# tb_projekt_rf433_shield_mini_revA.net
KiCad netlist of a schematic drawn in EAGLE
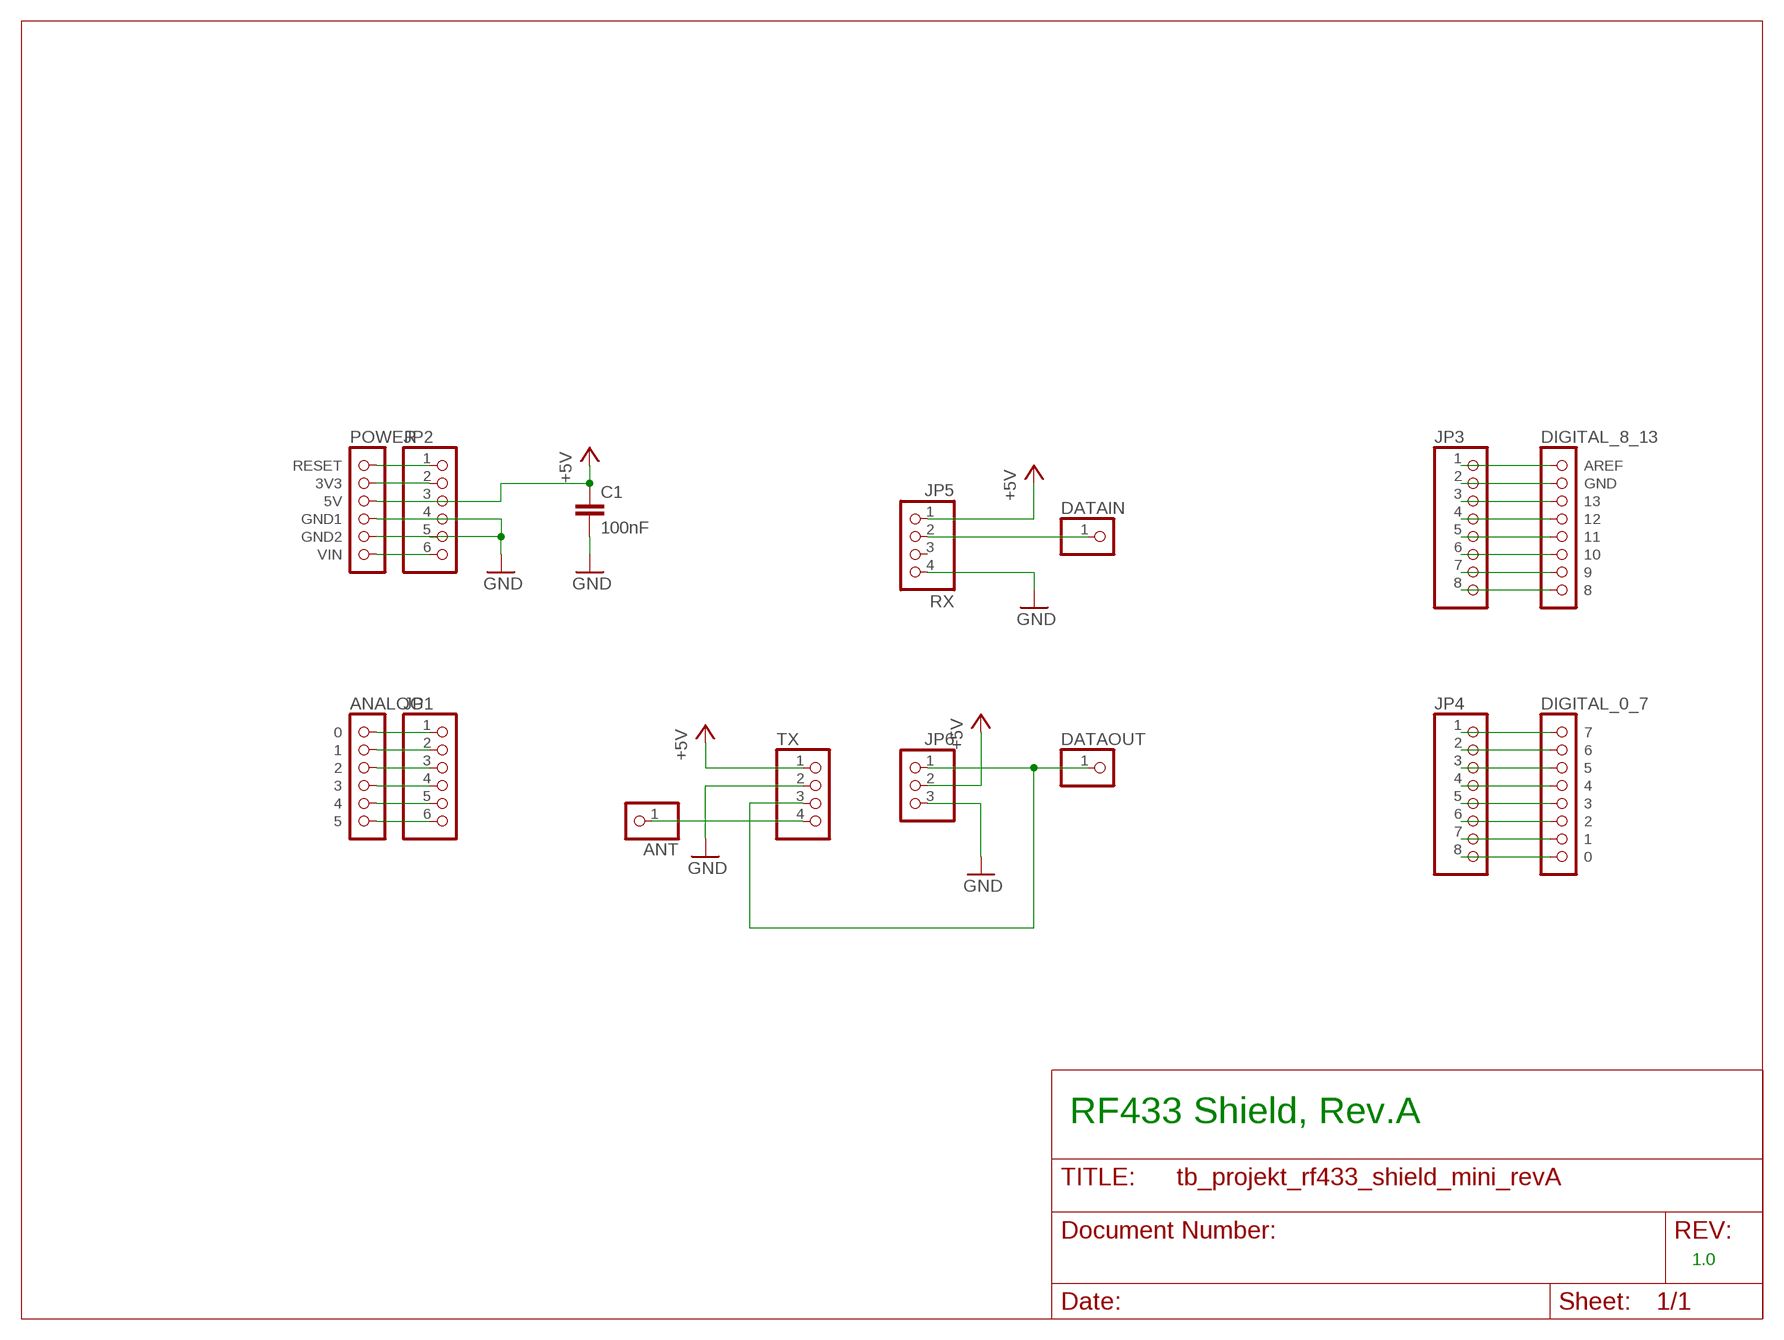
[diagram p0: schematic, sheet 1]

(export (version "E")
  (design (tool "Eeschema 10.0.6"))
  (components
    (comp (ref "ANT")
      (value "PINHD-1X1")
      (footprint "eagle-import:1X01")
      (libsource (lib "eagle-import") (part "PINHD-1X1"))
    )
    (comp (ref "C1")
      (value "100nF")
      (footprint "eagle-import:C025-024X044")
      (libsource (lib "eagle-import") (part "C-EU025-024X044"))
    )
    (comp (ref "DATAIN")
      (value "PINHD-1X1")
      (footprint "eagle-import:1X01")
      (libsource (lib "eagle-import") (part "PINHD-1X1"))
    )
    (comp (ref "DATAOUT")
      (value "PINHD-1X1")
      (footprint "eagle-import:1X01")
      (libsource (lib "eagle-import") (part "PINHD-1X1"))
    )
    (comp (ref "JP1")
      (value "PINHD-1X6")
      (footprint "eagle-import:1X06")
      (libsource (lib "eagle-import") (part "PINHD-1X6"))
    )
    (comp (ref "JP2")
      (value "PINHD-1X6")
      (footprint "eagle-import:1X06")
      (libsource (lib "eagle-import") (part "PINHD-1X6"))
    )
    (comp (ref "JP3")
      (value "PINHD-1X8")
      (footprint "eagle-import:1X08")
      (libsource (lib "eagle-import") (part "PINHD-1X8"))
    )
    (comp (ref "JP4")
      (value "PINHD-1X8")
      (footprint "eagle-import:1X08")
      (libsource (lib "eagle-import") (part "PINHD-1X8"))
    )
    (comp (ref "JP5")
      (value "RX")
      (footprint "eagle-import:1X04")
      (libsource (lib "eagle-import") (part "PINHD-1X4"))
    )
    (comp (ref "JP6")
      (value "PINHD-1X3")
      (footprint "eagle-import:1X03")
      (libsource (lib "eagle-import") (part "PINHD-1X3"))
    )
    (comp (ref "TX")
      (value "PINHD-1X4")
      (footprint "eagle-import:1X04")
      (libsource (lib "eagle-import") (part "PINHD-1X4"))
    )
    (comp (ref "U$1")
      (value "POWER")
      (footprint "eagle-import:1X06")
      (libsource (lib "eagle-import") (part "POWER"))
    )
    (comp (ref "U$2")
      (value "ANALOG")
      (footprint "eagle-import:1X06")
      (libsource (lib "eagle-import") (part "ANALOG"))
    )
    (comp (ref "U$3")
      (value "DIGITAL_0_7")
      (footprint "eagle-import:1X08")
      (libsource (lib "eagle-import") (part "DIGITAL_0_7"))
    )
    (comp (ref "U$4")
      (value "DIGITAL_8_13")
      (footprint "eagle-import:1X08")
      (libsource (lib "eagle-import") (part "DIGITAL_8_13"))
    )
  )
  (nets
    (net (code "1") (name "+5V") (class "Default")
      (node (ref "C1") (pin "1") (pinfunction "1_1") (pintype "passive"))
      (node (ref "JP2") (pin "3") (pinfunction "3_3") (pintype "passive"))
      (node (ref "JP5") (pin "1") (pinfunction "1_1") (pintype "passive"))
      (node (ref "JP6") (pin "2") (pinfunction "2_2") (pintype "passive"))
      (node (ref "TX") (pin "1") (pinfunction "1_1") (pintype "passive"))
      (node (ref "U$1") (pin "3") (pinfunction "5V_3") (pintype "passive"))
    )
    (net (code "2") (name "GND") (class "Default")
      (node (ref "C1") (pin "2") (pinfunction "2_2") (pintype "passive"))
      (node (ref "JP2") (pin "4") (pinfunction "4_4") (pintype "passive"))
      (node (ref "JP2") (pin "5") (pinfunction "5_5") (pintype "passive"))
      (node (ref "JP5") (pin "4") (pinfunction "4_4") (pintype "passive"))
      (node (ref "JP6") (pin "3") (pinfunction "3_3") (pintype "passive"))
      (node (ref "TX") (pin "2") (pinfunction "2_2") (pintype "passive"))
      (node (ref "U$1") (pin "4") (pinfunction "GND1_4") (pintype "passive"))
      (node (ref "U$1") (pin "5") (pinfunction "GND2_5") (pintype "passive"))
    )
    (net (code "3") (name "Net-(ANT-Pad1)") (class "Default")
      (node (ref "ANT") (pin "1") (pinfunction "1_1") (pintype "passive"))
      (node (ref "TX") (pin "4") (pinfunction "4_4") (pintype "passive"))
    )
    (net (code "4") (name "Net-(DATAIN-Pad1)") (class "Default")
      (node (ref "DATAIN") (pin "1") (pinfunction "1_1") (pintype "passive"))
      (node (ref "JP5") (pin "2") (pinfunction "2_2") (pintype "passive"))
    )
    (net (code "5") (name "Net-(DATAOUT-Pad1)") (class "Default")
      (node (ref "DATAOUT") (pin "1") (pinfunction "1_1") (pintype "passive"))
      (node (ref "JP6") (pin "1") (pinfunction "1_1") (pintype "passive"))
      (node (ref "TX") (pin "3") (pinfunction "3_3") (pintype "passive"))
    )
    (net (code "6") (name "Net-(JP3-Pad8)") (class "Default")
      (node (ref "JP3") (pin "8") (pinfunction "8_8") (pintype "passive"))
      (node (ref "U$4") (pin "8") (pinfunction "8_8") (pintype "passive"))
    )
    (net (code "7") (name "Net-(JP4-Pad4)") (class "Default")
      (node (ref "JP4") (pin "4") (pinfunction "4_4") (pintype "passive"))
      (node (ref "U$3") (pin "4") (pinfunction "4_4") (pintype "passive"))
    )
    (net (code "8") (name "Net-(U$1-3V3)") (class "Default")
      (node (ref "JP2") (pin "2") (pinfunction "2_2") (pintype "passive"))
      (node (ref "U$1") (pin "2") (pinfunction "3V3_2") (pintype "passive"))
    )
    (net (code "9") (name "Net-(U$1-RESET)") (class "Default")
      (node (ref "JP2") (pin "1") (pinfunction "1_1") (pintype "passive"))
      (node (ref "U$1") (pin "1") (pinfunction "RESET_1") (pintype "passive"))
    )
    (net (code "10") (name "Net-(U$1-VIN)") (class "Default")
      (node (ref "JP2") (pin "6") (pinfunction "6_6") (pintype "passive"))
      (node (ref "U$1") (pin "6") (pinfunction "VIN_6") (pintype "passive"))
    )
    (net (code "11") (name "Net-(U$2-0)") (class "Default")
      (node (ref "JP1") (pin "1") (pinfunction "1_1") (pintype "passive"))
      (node (ref "U$2") (pin "1") (pinfunction "0_1") (pintype "passive"))
    )
    (net (code "12") (name "Net-(U$2-1)") (class "Default")
      (node (ref "JP1") (pin "2") (pinfunction "2_2") (pintype "passive"))
      (node (ref "U$2") (pin "2") (pinfunction "1_2") (pintype "passive"))
    )
    (net (code "13") (name "Net-(U$2-2)") (class "Default")
      (node (ref "JP1") (pin "3") (pinfunction "3_3") (pintype "passive"))
      (node (ref "U$2") (pin "3") (pinfunction "2_3") (pintype "passive"))
    )
    (net (code "14") (name "Net-(U$2-3)") (class "Default")
      (node (ref "JP1") (pin "4") (pinfunction "4_4") (pintype "passive"))
      (node (ref "U$2") (pin "4") (pinfunction "3_4") (pintype "passive"))
    )
    (net (code "15") (name "Net-(U$2-4)") (class "Default")
      (node (ref "JP1") (pin "5") (pinfunction "5_5") (pintype "passive"))
      (node (ref "U$2") (pin "5") (pinfunction "4_5") (pintype "passive"))
    )
    (net (code "16") (name "Net-(U$2-5)") (class "Default")
      (node (ref "JP1") (pin "6") (pinfunction "6_6") (pintype "passive"))
      (node (ref "U$2") (pin "6") (pinfunction "5_6") (pintype "passive"))
    )
    (net (code "17") (name "Net-(U$3-0)") (class "Default")
      (node (ref "JP4") (pin "8") (pinfunction "8_8") (pintype "passive"))
      (node (ref "U$3") (pin "8") (pinfunction "0_8") (pintype "passive"))
    )
    (net (code "18") (name "Net-(U$3-1)") (class "Default")
      (node (ref "JP4") (pin "7") (pinfunction "7_7") (pintype "passive"))
      (node (ref "U$3") (pin "7") (pinfunction "1_7") (pintype "passive"))
    )
    (net (code "19") (name "Net-(U$3-2)") (class "Default")
      (node (ref "JP4") (pin "6") (pinfunction "6_6") (pintype "passive"))
      (node (ref "U$3") (pin "6") (pinfunction "2_6") (pintype "passive"))
    )
    (net (code "20") (name "Net-(U$3-3)") (class "Default")
      (node (ref "JP4") (pin "5") (pinfunction "5_5") (pintype "passive"))
      (node (ref "U$3") (pin "5") (pinfunction "3_5") (pintype "passive"))
    )
    (net (code "21") (name "Net-(U$3-5)") (class "Default")
      (node (ref "JP4") (pin "3") (pinfunction "3_3") (pintype "passive"))
      (node (ref "U$3") (pin "3") (pinfunction "5_3") (pintype "passive"))
    )
    (net (code "22") (name "Net-(U$3-6)") (class "Default")
      (node (ref "JP4") (pin "2") (pinfunction "2_2") (pintype "passive"))
      (node (ref "U$3") (pin "2") (pinfunction "6_2") (pintype "passive"))
    )
    (net (code "23") (name "Net-(U$3-7)") (class "Default")
      (node (ref "JP4") (pin "1") (pinfunction "1_1") (pintype "passive"))
      (node (ref "U$3") (pin "1") (pinfunction "7_1") (pintype "passive"))
    )
    (net (code "24") (name "Net-(U$4-9)") (class "Default")
      (node (ref "JP3") (pin "7") (pinfunction "7_7") (pintype "passive"))
      (node (ref "U$4") (pin "7") (pinfunction "9_7") (pintype "passive"))
    )
    (net (code "25") (name "Net-(U$4-10)") (class "Default")
      (node (ref "JP3") (pin "6") (pinfunction "6_6") (pintype "passive"))
      (node (ref "U$4") (pin "6") (pinfunction "10_6") (pintype "passive"))
    )
    (net (code "26") (name "Net-(U$4-11)") (class "Default")
      (node (ref "JP3") (pin "5") (pinfunction "5_5") (pintype "passive"))
      (node (ref "U$4") (pin "5") (pinfunction "11_5") (pintype "passive"))
    )
    (net (code "27") (name "Net-(U$4-12)") (class "Default")
      (node (ref "JP3") (pin "4") (pinfunction "4_4") (pintype "passive"))
      (node (ref "U$4") (pin "4") (pinfunction "12_4") (pintype "passive"))
    )
    (net (code "28") (name "Net-(U$4-13)") (class "Default")
      (node (ref "JP3") (pin "3") (pinfunction "3_3") (pintype "passive"))
      (node (ref "U$4") (pin "3") (pinfunction "13_3") (pintype "passive"))
    )
    (net (code "29") (name "Net-(U$4-AREF)") (class "Default")
      (node (ref "JP3") (pin "1") (pinfunction "1_1") (pintype "passive"))
      (node (ref "U$4") (pin "1") (pinfunction "AREF_1") (pintype "passive"))
    )
    (net (code "30") (name "Net-(U$4-GND)") (class "Default")
      (node (ref "JP3") (pin "2") (pinfunction "2_2") (pintype "passive"))
      (node (ref "U$4") (pin "2") (pinfunction "GND_2") (pintype "passive"))
    )
    (net (code "31") (name "unconnected-(JP5-Pad3)") (class "Default")
      (node (ref "JP5") (pin "3") (pinfunction "3_3") (pintype "passive"))
    )
  )
)
